# eX_ESP_Robot.net
KiCad netlist of a schematic drawn in EAGLE
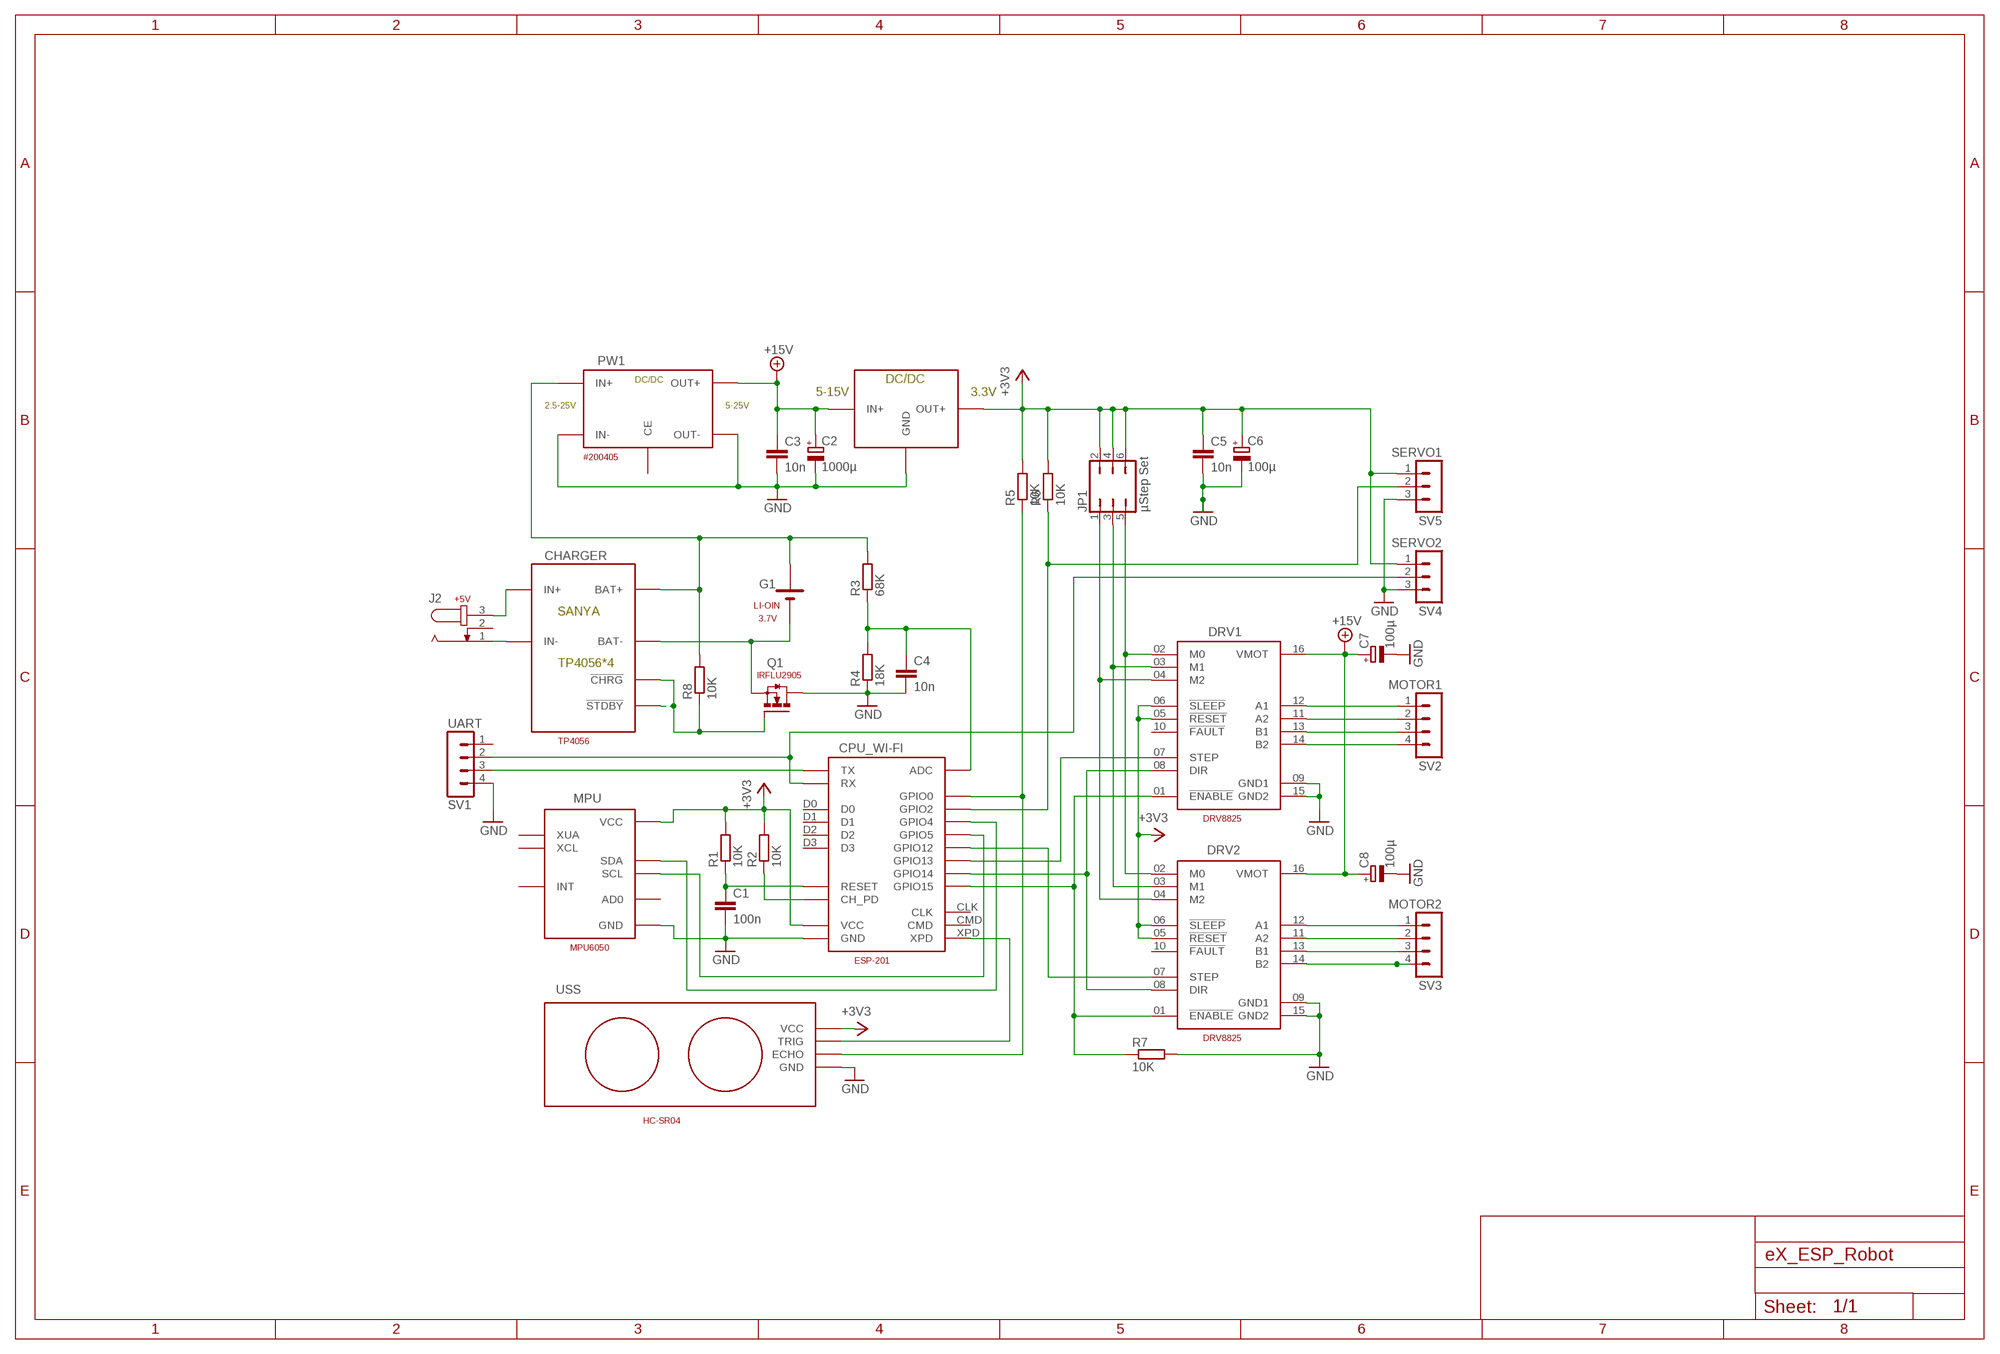
[diagram p0: schematic, sheet 1]

(export (version "E")
  (design (tool "Eeschema 10.0.6"))
  (components
    (comp (ref "C1")
      (value "100n")
      (footprint "eagle-import:C025-024X044")
      (libsource (lib "eagle-import") (part "C-EU025-024X044"))
    )
    (comp (ref "C2")
      (value "1000µ")
      (footprint "eagle-import:TT5D6")
      (libsource (lib "eagle-import") (part "CPOL-EUTT6D6"))
    )
    (comp (ref "C3")
      (value "10n")
      (footprint "eagle-import:C025-025X050")
      (libsource (lib "eagle-import") (part "C-EU025-025X050"))
    )
    (comp (ref "C4")
      (value "10n")
      (footprint "eagle-import:C025-025X050")
      (libsource (lib "eagle-import") (part "C-EU025-025X050"))
    )
    (comp (ref "C5")
      (value "10n")
      (footprint "eagle-import:C025-025X050")
      (libsource (lib "eagle-import") (part "C-EU025-025X050"))
    )
    (comp (ref "C6")
      (value "100µ")
      (footprint "eagle-import:TT5D6")
      (libsource (lib "eagle-import") (part "CPOL-EUTT6D6"))
    )
    (comp (ref "C7")
      (value "100µ")
      (footprint "eagle-import:TT2D4")
      (libsource (lib "eagle-import") (part "CPOL-EUTT2D4"))
    )
    (comp (ref "C8")
      (value "100µ")
      (footprint "eagle-import:TT2D4")
      (libsource (lib "eagle-import") (part "CPOL-EUTT2D4"))
    )
    (comp (ref "CHARGER")
      (value "TP4056")
      (footprint "eagle-import:TP4056")
      (libsource (lib "eagle-import") (part "TP4056"))
    )
    (comp (ref "CPU_WI-FI")
      (value "ESP-201")
      (footprint "eagle-import:ESP-201")
      (libsource (lib "eagle-import") (part "ESP-201"))
    )
    (comp (ref "DRV1")
      (value "DRV8825")
      (footprint "eagle-import:DRV8825")
      (libsource (lib "eagle-import") (part "DRV8825"))
    )
    (comp (ref "DRV2")
      (value "DRV8825")
      (footprint "eagle-import:DRV8825")
      (libsource (lib "eagle-import") (part "DRV8825"))
    )
    (comp (ref "G1")
      (value "LI-OIN")
      (footprint "eagle-import:LI-ION")
      (fields (field (name "VOLTAGE") "3.7V"))
      (libsource (lib "eagle-import") (part "LI-OIN"))
    )
    (comp (ref "J2")
      (value "+5V")
      (footprint "eagle-import:SPC4077")
      (libsource (lib "eagle-import") (part "JACK-PLUG0"))
    )
    (comp (ref "JP1")
      (value "µStep Set")
      (footprint "eagle-import:JP3Q")
      (libsource (lib "eagle-import") (part "JP3Q"))
    )
    (comp (ref "MPU")
      (value "MPU-6050")
      (footprint "eagle-import:MPU-6050")
      (libsource (lib "eagle-import") (part "MPU-6050"))
    )
    (comp (ref "PW1")
      (value "#200405")
      (footprint "eagle-import:#200405")
      (libsource (lib "eagle-import") (part "#200405"))
    )
    (comp (ref "Q1")
      (value "N-HEXFET-2D_SOT232-IRLL2705")
      (footprint "eagle-import:SOT223")
      (fields (field (name "TYPE") "IRFLU2905"))
      (libsource (lib "eagle-import") (part "N-HEXFET-2D_?-SOT232IRLL2705"))
    )
    (comp (ref "R1")
      (value "10K")
      (footprint "eagle-import:0204_5")
      (libsource (lib "eagle-import") (part "R-EU_0204/5"))
    )
    (comp (ref "R2")
      (value "10K")
      (footprint "eagle-import:0204_5")
      (libsource (lib "eagle-import") (part "R-EU_0204/5"))
    )
    (comp (ref "R3")
      (value "68K")
      (footprint "eagle-import:0204_5")
      (libsource (lib "eagle-import") (part "R-EU_0204/5"))
    )
    (comp (ref "R4")
      (value "18K")
      (footprint "eagle-import:0204_5")
      (libsource (lib "eagle-import") (part "R-EU_0204/5"))
    )
    (comp (ref "R5")
      (value "10K")
      (footprint "eagle-import:0204_5")
      (libsource (lib "eagle-import") (part "R-EU_0204/5"))
    )
    (comp (ref "R6")
      (value "10K")
      (footprint "eagle-import:0204_5")
      (libsource (lib "eagle-import") (part "R-EU_0204/5"))
    )
    (comp (ref "R7")
      (value "10K")
      (footprint "eagle-import:0204_5")
      (libsource (lib "eagle-import") (part "R-EU_0204/5"))
    )
    (comp (ref "R8")
      (value "10K")
      (footprint "eagle-import:0204_5")
      (libsource (lib "eagle-import") (part "R-EU_0204/5"))
    )
    (comp (ref "SV1")
      (value "UART")
      (footprint "eagle-import:MA04-1")
      (libsource (lib "eagle-import") (part "MA04-1"))
    )
    (comp (ref "SV2")
      (value "MOTOR1")
      (footprint "eagle-import:MA04-1")
      (libsource (lib "eagle-import") (part "MA04-1"))
    )
    (comp (ref "SV3")
      (value "MOTOR2")
      (footprint "eagle-import:MA04-1")
      (libsource (lib "eagle-import") (part "MA04-1"))
    )
    (comp (ref "SV4")
      (value "SERVO2")
      (footprint "eagle-import:MA03-1")
      (libsource (lib "eagle-import") (part "MA03-1"))
    )
    (comp (ref "SV5")
      (value "SERVO1")
      (footprint "eagle-import:MA03-1")
      (libsource (lib "eagle-import") (part "MA03-1"))
    )
    (comp (ref "U$1")
      (value "YCO6001-3.3")
      (footprint "eagle-import:YCO6001-3.3")
      (libsource (lib "eagle-import") (part "YCO6001-3.3"))
    )
    (comp (ref "USS")
      (value "HC-SR04")
      (footprint "eagle-import:HC-SR04_FOOTPRINT")
      (libsource (lib "eagle-import") (part "HC-SR04"))
    )
  )
  (nets
    (net (code "1") (name "+3V3") (class "Default")
      (node (ref "C5") (pin "1") (pinfunction "1_1") (pintype "passive"))
      (node (ref "C6") (pin "+") (pinfunction "+_+") (pintype "passive"))
      (node (ref "CPU_WI-FI") (pin "3V3") (pinfunction "VCC_3V3") (pintype "bidirectional"))
      (node (ref "CPU_WI-FI") (pin "3V3_2") (pinfunction "VCC_3V3_2") (pintype "bidirectional"))
      (node (ref "CPU_WI-FI") (pin "3V3_3") (pinfunction "VCC_3V3_3") (pintype "bidirectional"))
      (node (ref "DRV1") (pin "05") (pinfunction "~{RESET}_05") (pintype "input"))
      (node (ref "DRV1") (pin "06") (pinfunction "~{SLEEP}_06") (pintype "input"))
      (node (ref "DRV2") (pin "05") (pinfunction "~{RESET}_05") (pintype "input"))
      (node (ref "DRV2") (pin "06") (pinfunction "~{SLEEP}_06") (pintype "input"))
      (node (ref "JP1") (pin "2") (pinfunction "2_2") (pintype "passive"))
      (node (ref "JP1") (pin "4") (pinfunction "4_4") (pintype "passive"))
      (node (ref "JP1") (pin "6") (pinfunction "6_6") (pintype "passive"))
      (node (ref "MPU") (pin "VCC") (pinfunction "VCC_VCC") (pintype "power_in"))
      (node (ref "R1") (pin "2") (pinfunction "2_2") (pintype "passive"))
      (node (ref "R2") (pin "2") (pinfunction "2_2") (pintype "passive"))
      (node (ref "R5") (pin "2") (pinfunction "2_2") (pintype "passive"))
      (node (ref "R6") (pin "2") (pinfunction "2_2") (pintype "passive"))
      (node (ref "SV4") (pin "1") (pinfunction "1_1") (pintype "passive"))
      (node (ref "SV5") (pin "1") (pinfunction "1_1") (pintype "passive"))
      (node (ref "U$1") (pin "OUT+1") (pinfunction "OUT+_OUT+1") (pintype "power_in"))
      (node (ref "U$1") (pin "OUT+2") (pinfunction "OUT+_OUT+2") (pintype "power_in"))
      (node (ref "USS") (pin "VCC") (pinfunction "VCC_VCC") (pintype "power_in"))
    )
    (net (code "2") (name "+15V") (class "Default")
      (node (ref "C2") (pin "+") (pinfunction "+_+") (pintype "passive"))
      (node (ref "C3") (pin "1") (pinfunction "1_1") (pintype "passive"))
      (node (ref "C7") (pin "+") (pinfunction "+_+") (pintype "passive"))
      (node (ref "C8") (pin "+") (pinfunction "+_+") (pintype "passive"))
      (node (ref "DRV1") (pin "16") (pinfunction "VMOT_16") (pintype "power_in"))
      (node (ref "DRV2") (pin "16") (pinfunction "VMOT_16") (pintype "power_in"))
      (node (ref "PW1") (pin "OUT+1") (pinfunction "OUT+_OUT+1") (pintype "power_in"))
      (node (ref "PW1") (pin "OUT+2") (pinfunction "OUT+_OUT+2") (pintype "power_in"))
      (node (ref "U$1") (pin "IN+1") (pinfunction "IN+_IN+1") (pintype "power_in"))
      (node (ref "U$1") (pin "IN+2") (pinfunction "IN+_IN+2") (pintype "power_in"))
    )
    (net (code "3") (name "GND") (class "Default")
      (node (ref "C1") (pin "2") (pinfunction "2_2") (pintype "passive"))
      (node (ref "C2") (pin "-") (pinfunction "-_-") (pintype "passive"))
      (node (ref "C3") (pin "2") (pinfunction "2_2") (pintype "passive"))
      (node (ref "C4") (pin "2") (pinfunction "2_2") (pintype "passive"))
      (node (ref "C5") (pin "2") (pinfunction "2_2") (pintype "passive"))
      (node (ref "C6") (pin "-") (pinfunction "-_-") (pintype "passive"))
      (node (ref "C7") (pin "-") (pinfunction "-_-") (pintype "passive"))
      (node (ref "C8") (pin "-") (pinfunction "-_-") (pintype "passive"))
      (node (ref "CPU_WI-FI") (pin "GND") (pinfunction "GND_GND") (pintype "bidirectional"))
      (node (ref "CPU_WI-FI") (pin "GND_2") (pinfunction "GND_GND_2") (pintype "bidirectional"))
      (node (ref "CPU_WI-FI") (pin "GND_3") (pinfunction "GND_GND_3") (pintype "bidirectional"))
      (node (ref "DRV1") (pin "09") (pinfunction "GND1_09") (pintype "power_in"))
      (node (ref "DRV1") (pin "15") (pinfunction "GND2_15") (pintype "power_in"))
      (node (ref "DRV2") (pin "09") (pinfunction "GND1_09") (pintype "power_in"))
      (node (ref "DRV2") (pin "15") (pinfunction "GND2_15") (pintype "power_in"))
      (node (ref "MPU") (pin "GND") (pinfunction "GND_GND") (pintype "power_in"))
      (node (ref "PW1") (pin "-IN1") (pinfunction "IN-_-IN1") (pintype "power_in"))
      (node (ref "PW1") (pin "-IN2") (pinfunction "IN-_-IN2") (pintype "power_in"))
      (node (ref "PW1") (pin "-IN3") (pinfunction "IN-_-IN3") (pintype "power_in"))
      (node (ref "PW1") (pin "-OUT1") (pinfunction "OUT-_-OUT1") (pintype "power_in"))
      (node (ref "PW1") (pin "-OUT2") (pinfunction "OUT-_-OUT2") (pintype "power_in"))
      (node (ref "PW1") (pin "-OUT3") (pinfunction "OUT-_-OUT3") (pintype "power_in"))
      (node (ref "Q1") (pin "2") (pinfunction "D_2") (pintype "passive"))
      (node (ref "Q1") (pin "4") (pinfunction "D_4") (pintype "passive"))
      (node (ref "R4") (pin "1") (pinfunction "1_1") (pintype "passive"))
      (node (ref "R7") (pin "2") (pinfunction "2_2") (pintype "passive"))
      (node (ref "SV1") (pin "4") (pinfunction "4_4") (pintype "passive"))
      (node (ref "SV4") (pin "3") (pinfunction "3_3") (pintype "passive"))
      (node (ref "SV5") (pin "3") (pinfunction "3_3") (pintype "passive"))
      (node (ref "U$1") (pin "IN-") (pinfunction "GND_IN-") (pintype "bidirectional"))
      (node (ref "U$1") (pin "OUT-") (pinfunction "GND_OUT-") (pintype "bidirectional"))
      (node (ref "USS") (pin "GND") (pinfunction "GND_GND") (pintype "power_in"))
    )
    (net (code "4") (name "Net-(C4-Pad1)") (class "Default")
      (node (ref "C4") (pin "1") (pinfunction "1_1") (pintype "passive"))
      (node (ref "CPU_WI-FI") (pin "ADC") (pinfunction "ADC_ADC") (pintype "bidirectional"))
      (node (ref "R3") (pin "1") (pinfunction "1_1") (pintype "passive"))
      (node (ref "R4") (pin "2") (pinfunction "2_2") (pintype "passive"))
    )
    (net (code "5") (name "Net-(CHARGER-BAT+)") (class "Default")
      (node (ref "CHARGER") (pin "B+") (pinfunction "BAT+_B+") (pintype "power_in"))
      (node (ref "G1") (pin "+1") (pinfunction "+_+1") (pintype "power_in"))
      (node (ref "G1") (pin "+2") (pinfunction "+_+2") (pintype "power_in"))
      (node (ref "PW1") (pin "IN+1") (pinfunction "IN+_IN+1") (pintype "power_in"))
      (node (ref "PW1") (pin "IN+2") (pinfunction "IN+_IN+2") (pintype "power_in"))
      (node (ref "PW1") (pin "IN+3") (pinfunction "IN+_IN+3") (pintype "power_in"))
      (node (ref "R3") (pin "2") (pinfunction "2_2") (pintype "passive"))
      (node (ref "R8") (pin "2") (pinfunction "2_2") (pintype "passive"))
    )
    (net (code "6") (name "Net-(CHARGER-BAT-)") (class "Default")
      (node (ref "CHARGER") (pin "B-") (pinfunction "BAT-_B-") (pintype "power_in"))
      (node (ref "G1") (pin "-1") (pinfunction "-_-1") (pintype "power_in"))
      (node (ref "G1") (pin "-2") (pinfunction "-_-2") (pintype "power_in"))
      (node (ref "Q1") (pin "3") (pinfunction "S_3") (pintype "passive"))
    )
    (net (code "7") (name "Net-(CHARGER-IN+-Pad5V+)") (class "Default")
      (node (ref "CHARGER") (pin "5V+") (pinfunction "IN+_5V+") (pintype "power_in"))
      (node (ref "CHARGER") (pin "V+") (pinfunction "IN+_V+") (pintype "power_in"))
      (node (ref "J2") (pin "3") (pinfunction "3_3") (pintype "passive"))
    )
    (net (code "8") (name "Net-(CHARGER-IN-)") (class "Default")
      (node (ref "CHARGER") (pin "5V-") (pinfunction "IN-_5V-") (pintype "power_in"))
      (node (ref "J2") (pin "1") (pinfunction "1_1") (pintype "passive"))
    )
    (net (code "9") (name "Net-(CHARGER-~{CHRG})") (class "Default")
      (node (ref "CHARGER") (pin "G") (pinfunction "~{STDBY}_G") (pintype "output"))
      (node (ref "CHARGER") (pin "R") (pinfunction "~{CHRG}_R") (pintype "output"))
      (node (ref "Q1") (pin "1") (pinfunction "G_1") (pintype "passive"))
      (node (ref "R8") (pin "1") (pinfunction "1_1") (pintype "passive"))
    )
    (net (code "10") (name "Net-(CPU_WI-FI-PadCH_PD)") (class "Default")
      (node (ref "CPU_WI-FI") (pin "CH_PD") (pinfunction "CH_PD_CH_PD") (pintype "bidirectional"))
      (node (ref "R2") (pin "1") (pinfunction "1_1") (pintype "passive"))
    )
    (net (code "11") (name "Net-(CPU_WI-FI-PadGPIO0)") (class "Default")
      (node (ref "CPU_WI-FI") (pin "GPIO0") (pinfunction "GPIO0_GPIO0") (pintype "bidirectional"))
      (node (ref "R5") (pin "1") (pinfunction "1_1") (pintype "passive"))
      (node (ref "USS") (pin "ECHO") (pinfunction "ECHO_ECHO") (pintype "output"))
    )
    (net (code "12") (name "Net-(CPU_WI-FI-PadGPIO2)") (class "Default")
      (node (ref "CPU_WI-FI") (pin "GPIO2") (pinfunction "GPIO2_GPIO2") (pintype "bidirectional"))
      (node (ref "R6") (pin "1") (pinfunction "1_1") (pintype "passive"))
      (node (ref "SV5") (pin "2") (pinfunction "2_2") (pintype "passive"))
    )
    (net (code "13") (name "Net-(CPU_WI-FI-PadGPIO4)") (class "Default")
      (node (ref "CPU_WI-FI") (pin "GPIO4") (pinfunction "GPIO4_GPIO4") (pintype "bidirectional"))
      (node (ref "MPU") (pin "SDA") (pinfunction "SDA_SDA") (pintype "bidirectional"))
    )
    (net (code "14") (name "Net-(CPU_WI-FI-PadGPIO5)") (class "Default")
      (node (ref "CPU_WI-FI") (pin "GPIO5") (pinfunction "GPIO5_GPIO5") (pintype "bidirectional"))
      (node (ref "MPU") (pin "SCL") (pinfunction "SCL_SCL") (pintype "bidirectional"))
    )
    (net (code "15") (name "Net-(CPU_WI-FI-PadRX)") (class "Default")
      (node (ref "CPU_WI-FI") (pin "RX") (pinfunction "RX_RX") (pintype "bidirectional"))
      (node (ref "SV1") (pin "2") (pinfunction "2_2") (pintype "passive"))
      (node (ref "SV4") (pin "2") (pinfunction "2_2") (pintype "passive"))
    )
    (net (code "16") (name "Net-(CPU_WI-FI-PadTX)") (class "Default")
      (node (ref "CPU_WI-FI") (pin "TX") (pinfunction "TX_TX") (pintype "bidirectional"))
      (node (ref "SV1") (pin "3") (pinfunction "3_3") (pintype "passive"))
    )
    (net (code "17") (name "Net-(CPU_WI-FI-PadXPD)") (class "Default")
      (node (ref "CPU_WI-FI") (pin "XPD") (pinfunction "XPD_XPD") (pintype "bidirectional"))
      (node (ref "USS") (pin "TRIG") (pinfunction "TRIG_TRIG") (pintype "input"))
    )
    (net (code "18") (name "Net-(CPU_WI-FI-RESET)") (class "Default")
      (node (ref "C1") (pin "1") (pinfunction "1_1") (pintype "passive"))
      (node (ref "CPU_WI-FI") (pin "RST") (pinfunction "RESET_RST") (pintype "bidirectional"))
      (node (ref "R1") (pin "1") (pinfunction "1_1") (pintype "passive"))
    )
    (net (code "19") (name "Net-(DRV1-A1)") (class "Default")
      (node (ref "DRV1") (pin "12") (pinfunction "A1_12") (pintype "output"))
      (node (ref "SV2") (pin "1") (pinfunction "1_1") (pintype "passive"))
    )
    (net (code "20") (name "Net-(DRV1-A2)") (class "Default")
      (node (ref "DRV1") (pin "11") (pinfunction "A2_11") (pintype "output"))
      (node (ref "SV2") (pin "2") (pinfunction "2_2") (pintype "passive"))
    )
    (net (code "21") (name "Net-(DRV1-B1)") (class "Default")
      (node (ref "DRV1") (pin "13") (pinfunction "B1_13") (pintype "output"))
      (node (ref "SV2") (pin "3") (pinfunction "3_3") (pintype "passive"))
    )
    (net (code "22") (name "Net-(DRV1-B2)") (class "Default")
      (node (ref "DRV1") (pin "14") (pinfunction "B2_14") (pintype "output"))
      (node (ref "SV2") (pin "4") (pinfunction "4_4") (pintype "passive"))
    )
    (net (code "23") (name "Net-(DRV1-DIR)") (class "Default")
      (node (ref "CPU_WI-FI") (pin "GPIO14") (pinfunction "GPIO14_GPIO14") (pintype "bidirectional"))
      (node (ref "DRV1") (pin "08") (pinfunction "DIR_08") (pintype "input"))
      (node (ref "DRV2") (pin "08") (pinfunction "DIR_08") (pintype "input"))
    )
    (net (code "24") (name "Net-(DRV1-M0)") (class "Default")
      (node (ref "DRV1") (pin "02") (pinfunction "M0_02") (pintype "input"))
      (node (ref "DRV2") (pin "02") (pinfunction "M0_02") (pintype "input"))
      (node (ref "JP1") (pin "5") (pinfunction "5_5") (pintype "passive"))
    )
    (net (code "25") (name "Net-(DRV1-M1)") (class "Default")
      (node (ref "DRV1") (pin "03") (pinfunction "M1_03") (pintype "input"))
      (node (ref "DRV2") (pin "03") (pinfunction "M1_03") (pintype "input"))
      (node (ref "JP1") (pin "3") (pinfunction "3_3") (pintype "passive"))
    )
    (net (code "26") (name "Net-(DRV1-M2)") (class "Default")
      (node (ref "DRV1") (pin "04") (pinfunction "M2_04") (pintype "input"))
      (node (ref "DRV2") (pin "04") (pinfunction "M2_04") (pintype "input"))
      (node (ref "JP1") (pin "1") (pinfunction "1_1") (pintype "passive"))
    )
    (net (code "27") (name "Net-(DRV1-STEP)") (class "Default")
      (node (ref "CPU_WI-FI") (pin "GPIO13") (pinfunction "GPIO13_GPIO13") (pintype "bidirectional"))
      (node (ref "DRV1") (pin "07") (pinfunction "STEP_07") (pintype "input"))
    )
    (net (code "28") (name "Net-(DRV1-~{ENABLE})") (class "Default")
      (node (ref "CPU_WI-FI") (pin "GPIO15") (pinfunction "GPIO15_GPIO15") (pintype "bidirectional"))
      (node (ref "DRV1") (pin "01") (pinfunction "~{ENABLE}_01") (pintype "input"))
      (node (ref "DRV2") (pin "01") (pinfunction "~{ENABLE}_01") (pintype "input"))
      (node (ref "R7") (pin "1") (pinfunction "1_1") (pintype "passive"))
    )
    (net (code "29") (name "Net-(DRV2-A1)") (class "Default")
      (node (ref "DRV2") (pin "12") (pinfunction "A1_12") (pintype "output"))
      (node (ref "SV3") (pin "1") (pinfunction "1_1") (pintype "passive"))
    )
    (net (code "30") (name "Net-(DRV2-A2)") (class "Default")
      (node (ref "DRV2") (pin "11") (pinfunction "A2_11") (pintype "output"))
      (node (ref "SV3") (pin "2") (pinfunction "2_2") (pintype "passive"))
    )
    (net (code "31") (name "Net-(DRV2-B1)") (class "Default")
      (node (ref "DRV2") (pin "13") (pinfunction "B1_13") (pintype "output"))
      (node (ref "SV3") (pin "3") (pinfunction "3_3") (pintype "passive"))
    )
    (net (code "32") (name "Net-(DRV2-B2)") (class "Default")
      (node (ref "DRV2") (pin "14") (pinfunction "B2_14") (pintype "output"))
      (node (ref "SV3") (pin "4") (pinfunction "4_4") (pintype "passive"))
    )
    (net (code "33") (name "Net-(DRV2-STEP)") (class "Default")
      (node (ref "CPU_WI-FI") (pin "GPIO12") (pinfunction "GPIO12_GPIO12") (pintype "bidirectional"))
      (node (ref "DRV2") (pin "07") (pinfunction "STEP_07") (pintype "input"))
    )
    (net (code "34") (name "unconnected-(CPU_WI-FI-PadCLK)") (class "Default")
      (node (ref "CPU_WI-FI") (pin "CLK") (pinfunction "CLK_CLK") (pintype "bidirectional"))
    )
    (net (code "35") (name "unconnected-(CPU_WI-FI-PadCMD)") (class "Default")
      (node (ref "CPU_WI-FI") (pin "CMD") (pinfunction "CMD_CMD") (pintype "bidirectional"))
    )
    (net (code "36") (name "unconnected-(CPU_WI-FI-PadD0)") (class "Default")
      (node (ref "CPU_WI-FI") (pin "D0") (pinfunction "D0_D0") (pintype "bidirectional"))
    )
    (net (code "37") (name "unconnected-(CPU_WI-FI-PadD1)") (class "Default")
      (node (ref "CPU_WI-FI") (pin "D1") (pinfunction "D1_D1") (pintype "bidirectional"))
    )
    (net (code "38") (name "unconnected-(CPU_WI-FI-PadD2)") (class "Default")
      (node (ref "CPU_WI-FI") (pin "D2") (pinfunction "D2_D2") (pintype "bidirectional"))
    )
    (net (code "39") (name "unconnected-(CPU_WI-FI-PadD3)") (class "Default")
      (node (ref "CPU_WI-FI") (pin "D3") (pinfunction "D3_D3") (pintype "bidirectional"))
    )
    (net (code "40") (name "unconnected-(DRV1-~{FAULT}-Pad10)") (class "Default")
      (node (ref "DRV1") (pin "10") (pinfunction "~{FAULT}_10") (pintype "bidirectional"))
    )
    (net (code "41") (name "unconnected-(DRV2-~{FAULT}-Pad10)") (class "Default")
      (node (ref "DRV2") (pin "10") (pinfunction "~{FAULT}_10") (pintype "bidirectional"))
    )
    (net (code "42") (name "unconnected-(J2-Pad2)") (class "Default")
      (node (ref "J2") (pin "2") (pinfunction "2_2") (pintype "passive"))
    )
    (net (code "43") (name "unconnected-(MPU-PadAD0)") (class "Default")
      (node (ref "MPU") (pin "AD0") (pinfunction "AD0_AD0") (pintype "input"))
    )
    (net (code "44") (name "unconnected-(MPU-PadINT)") (class "Default")
      (node (ref "MPU") (pin "INT") (pinfunction "INT_INT") (pintype "output"))
    )
    (net (code "45") (name "unconnected-(MPU-PadXCL)") (class "Default")
      (node (ref "MPU") (pin "XCL") (pinfunction "XCL_XCL") (pintype "bidirectional"))
    )
    (net (code "46") (name "unconnected-(MPU-XUA-PadXDA)") (class "Default")
      (node (ref "MPU") (pin "XDA") (pinfunction "XUA_XDA") (pintype "bidirectional"))
    )
    (net (code "47") (name "unconnected-(PW1-CE-PadON{slash}OFF)") (class "Default")
      (node (ref "PW1") (pin "ON/OFF") (pinfunction "CE_ON/OFF") (pintype "input"))
    )
    (net (code "48") (name "unconnected-(SV1-Pad1)") (class "Default")
      (node (ref "SV1") (pin "1") (pinfunction "1_1") (pintype "passive"))
    )
  )
)
